# Schematic.net
KiCad netlist of a schematic drawn in EAGLE
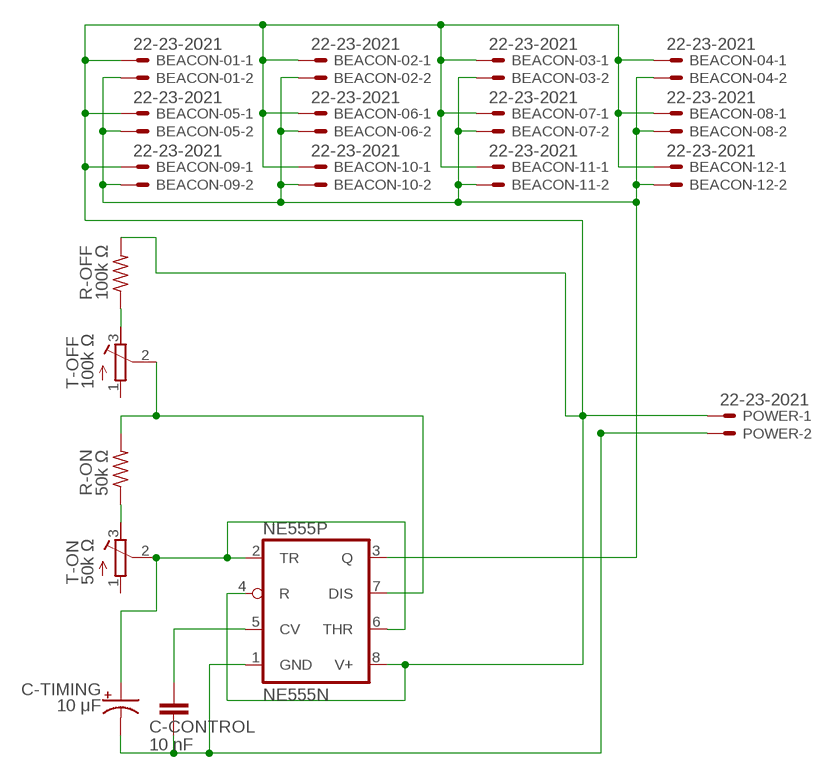
[diagram p0: schematic, sheet 1]

(export (version "E")
  (design (tool "Eeschema 10.0.6"))
  (components
    (comp (ref "BEACON-01")
      (value "22-23-2021")
      (footprint "eagle-import:22-23-2021")
      (fields (field (name "MF") "MOLEX"))
      (libsource (lib "eagle-import") (part "22-23-2021"))
    )
    (comp (ref "BEACON-02")
      (value "22-23-2021")
      (footprint "eagle-import:22-23-2021")
      (fields (field (name "MF") "MOLEX"))
      (libsource (lib "eagle-import") (part "22-23-2021"))
    )
    (comp (ref "BEACON-03")
      (value "22-23-2021")
      (footprint "eagle-import:22-23-2021")
      (fields (field (name "MF") "MOLEX"))
      (libsource (lib "eagle-import") (part "22-23-2021"))
    )
    (comp (ref "BEACON-04")
      (value "22-23-2021")
      (footprint "eagle-import:22-23-2021")
      (fields (field (name "MF") "MOLEX"))
      (libsource (lib "eagle-import") (part "22-23-2021"))
    )
    (comp (ref "BEACON-05")
      (value "22-23-2021")
      (footprint "eagle-import:22-23-2021")
      (fields (field (name "MF") "MOLEX"))
      (libsource (lib "eagle-import") (part "22-23-2021"))
    )
    (comp (ref "BEACON-06")
      (value "22-23-2021")
      (footprint "eagle-import:22-23-2021")
      (fields (field (name "MF") "MOLEX"))
      (libsource (lib "eagle-import") (part "22-23-2021"))
    )
    (comp (ref "BEACON-07")
      (value "22-23-2021")
      (footprint "eagle-import:22-23-2021")
      (fields (field (name "MF") "MOLEX"))
      (libsource (lib "eagle-import") (part "22-23-2021"))
    )
    (comp (ref "BEACON-08")
      (value "22-23-2021")
      (footprint "eagle-import:22-23-2021")
      (fields (field (name "MF") "MOLEX"))
      (libsource (lib "eagle-import") (part "22-23-2021"))
    )
    (comp (ref "BEACON-09")
      (value "22-23-2021")
      (footprint "eagle-import:22-23-2021")
      (fields (field (name "MF") "MOLEX"))
      (libsource (lib "eagle-import") (part "22-23-2021"))
    )
    (comp (ref "BEACON-10")
      (value "22-23-2021")
      (footprint "eagle-import:22-23-2021")
      (fields (field (name "MF") "MOLEX"))
      (libsource (lib "eagle-import") (part "22-23-2021"))
    )
    (comp (ref "BEACON-11")
      (value "22-23-2021")
      (footprint "eagle-import:22-23-2021")
      (fields (field (name "MF") "MOLEX"))
      (libsource (lib "eagle-import") (part "22-23-2021"))
    )
    (comp (ref "BEACON-12")
      (value "22-23-2021")
      (footprint "eagle-import:22-23-2021")
      (fields (field (name "MF") "MOLEX"))
      (libsource (lib "eagle-import") (part "22-23-2021"))
    )
    (comp (ref "C-CONTROL")
      (value "10 nF")
      (footprint "eagle-import:C2.5-2")
      (libsource (lib "eagle-import") (part "C2.5/2"))
    )
    (comp (ref "C-TIMING")
      (value "10 μF")
      (footprint "eagle-import:E2-5")
      (libsource (lib "eagle-import") (part "CPOL-USE2-5"))
    )
    (comp (ref "NE555P")
      (value "NE555N")
      (footprint "eagle-import:DIL08")
      (libsource (lib "eagle-import") (part "555NNE"))
    )
    (comp (ref "POWER")
      (value "22-23-2021")
      (footprint "eagle-import:22-23-2021")
      (fields (field (name "MF") "MOLEX"))
      (libsource (lib "eagle-import") (part "22-23-2021"))
    )
    (comp (ref "R-OFF")
      (value "100k Ω")
      (footprint "eagle-import:0207_7")
      (libsource (lib "eagle-import") (part "R-US_0207/7"))
    )
    (comp (ref "R-ON")
      (value "50k Ω")
      (footprint "eagle-import:0207_7")
      (libsource (lib "eagle-import") (part "R-US_0207/7"))
    )
    (comp (ref "T-OFF")
      (value "100k Ω")
      (footprint "eagle-import:RTRIM5X")
      (libsource (lib "eagle-import") (part "R-TRIMM5X"))
    )
    (comp (ref "T-ON")
      (value "50k Ω")
      (footprint "eagle-import:RTRIM5X")
      (libsource (lib "eagle-import") (part "R-TRIMM5X"))
    )
  )
  (nets
    (net (code "1") (name "Net-(BEACON-01A-S)") (class "Default")
      (node (ref "BEACON-01") (pin "1") (pinfunction "S_1") (pintype "passive"))
      (node (ref "BEACON-02") (pin "1") (pinfunction "S_1") (pintype "passive"))
      (node (ref "BEACON-03") (pin "1") (pinfunction "S_1") (pintype "passive"))
      (node (ref "BEACON-04") (pin "1") (pinfunction "S_1") (pintype "passive"))
      (node (ref "BEACON-05") (pin "1") (pinfunction "S_1") (pintype "passive"))
      (node (ref "BEACON-06") (pin "1") (pinfunction "S_1") (pintype "passive"))
      (node (ref "BEACON-07") (pin "1") (pinfunction "S_1") (pintype "passive"))
      (node (ref "BEACON-08") (pin "1") (pinfunction "S_1") (pintype "passive"))
      (node (ref "BEACON-09") (pin "1") (pinfunction "S_1") (pintype "passive"))
      (node (ref "BEACON-10") (pin "1") (pinfunction "S_1") (pintype "passive"))
      (node (ref "BEACON-11") (pin "1") (pinfunction "S_1") (pintype "passive"))
      (node (ref "BEACON-12") (pin "1") (pinfunction "S_1") (pintype "passive"))
      (node (ref "NE555P") (pin "4") (pinfunction "R_4") (pintype "input"))
      (node (ref "NE555P") (pin "8") (pinfunction "V+_8") (pintype "power_in"))
      (node (ref "POWER") (pin "1") (pinfunction "S_1") (pintype "passive"))
      (node (ref "R-OFF") (pin "2") (pinfunction "2_2") (pintype "passive"))
    )
    (net (code "2") (name "Net-(BEACON-01B-S)") (class "Default")
      (node (ref "BEACON-01") (pin "2") (pinfunction "S_2") (pintype "passive"))
      (node (ref "BEACON-02") (pin "2") (pinfunction "S_2") (pintype "passive"))
      (node (ref "BEACON-03") (pin "2") (pinfunction "S_2") (pintype "passive"))
      (node (ref "BEACON-04") (pin "2") (pinfunction "S_2") (pintype "passive"))
      (node (ref "BEACON-05") (pin "2") (pinfunction "S_2") (pintype "passive"))
      (node (ref "BEACON-06") (pin "2") (pinfunction "S_2") (pintype "passive"))
      (node (ref "BEACON-07") (pin "2") (pinfunction "S_2") (pintype "passive"))
      (node (ref "BEACON-08") (pin "2") (pinfunction "S_2") (pintype "passive"))
      (node (ref "BEACON-09") (pin "2") (pinfunction "S_2") (pintype "passive"))
      (node (ref "BEACON-10") (pin "2") (pinfunction "S_2") (pintype "passive"))
      (node (ref "BEACON-11") (pin "2") (pinfunction "S_2") (pintype "passive"))
      (node (ref "BEACON-12") (pin "2") (pinfunction "S_2") (pintype "passive"))
      (node (ref "NE555P") (pin "3") (pinfunction "Q_3") (pintype "output"))
    )
    (net (code "3") (name "Net-(NE555P-CV)") (class "Default")
      (node (ref "C-CONTROL") (pin "1") (pinfunction "1_1") (pintype "passive"))
      (node (ref "NE555P") (pin "5") (pinfunction "CV_5") (pintype "input"))
    )
    (net (code "4") (name "Net-(NE555P-DIS)") (class "Default")
      (node (ref "NE555P") (pin "7") (pinfunction "DIS_7") (pintype "input"))
      (node (ref "R-ON") (pin "2") (pinfunction "2_2") (pintype "passive"))
      (node (ref "T-OFF") (pin "2") (pinfunction "S_2") (pintype "passive"))
    )
    (net (code "5") (name "Net-(NE555P-GND)") (class "Default")
      (node (ref "C-CONTROL") (pin "2") (pinfunction "2_2") (pintype "passive"))
      (node (ref "C-TIMING") (pin "-") (pinfunction "-_-") (pintype "passive"))
      (node (ref "NE555P") (pin "1") (pinfunction "GND_1") (pintype "power_in"))
      (node (ref "POWER") (pin "2") (pinfunction "S_2") (pintype "passive"))
    )
    (net (code "6") (name "Net-(NE555P-THR)") (class "Default")
      (node (ref "C-TIMING") (pin "+") (pinfunction "+_+") (pintype "passive"))
      (node (ref "NE555P") (pin "2") (pinfunction "TR_2") (pintype "input"))
      (node (ref "NE555P") (pin "6") (pinfunction "THR_6") (pintype "input"))
      (node (ref "T-ON") (pin "2") (pinfunction "S_2") (pintype "passive"))
    )
    (net (code "7") (name "Net-(T-OFF-E)") (class "Default")
      (node (ref "R-OFF") (pin "1") (pinfunction "1_1") (pintype "passive"))
      (node (ref "T-OFF") (pin "3") (pinfunction "E_3") (pintype "passive"))
    )
    (net (code "8") (name "Net-(T-ON-E)") (class "Default")
      (node (ref "R-ON") (pin "1") (pinfunction "1_1") (pintype "passive"))
      (node (ref "T-ON") (pin "3") (pinfunction "E_3") (pintype "passive"))
    )
    (net (code "9") (name "unconnected-(T-OFF-A-Pad1)") (class "Default")
      (node (ref "T-OFF") (pin "1") (pinfunction "A_1") (pintype "passive"))
    )
    (net (code "10") (name "unconnected-(T-ON-A-Pad1)") (class "Default")
      (node (ref "T-ON") (pin "1") (pinfunction "A_1") (pintype "passive"))
    )
  )
)
